# Bottom_Board.net
KiCad netlist of a schematic drawn in EAGLE
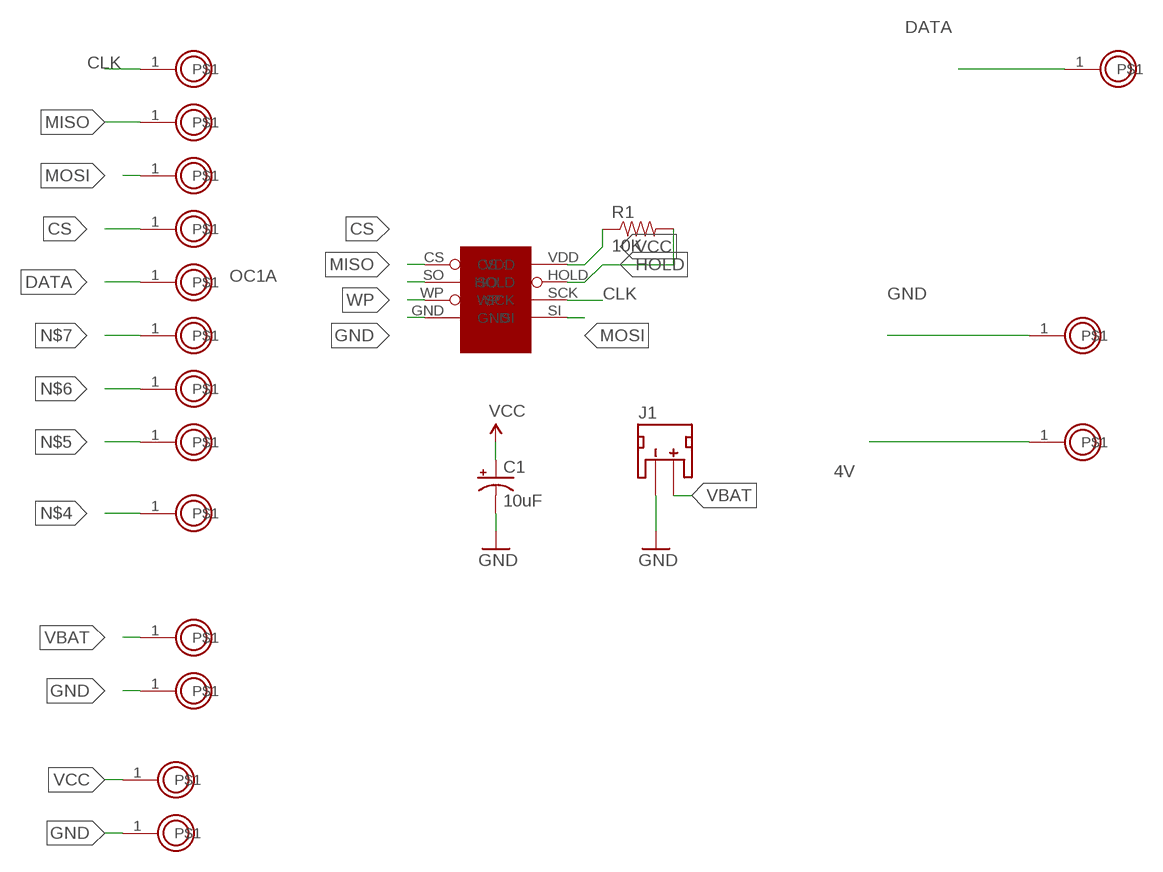
[diagram p0: schematic, sheet 1]

(export (version "E")
  (design (tool "Eeschema 10.0.6"))
  (components
    (comp (ref "0")
      (value "PROTO_POINT")
      (footprint "eagle-import:1X01")
      (libsource (lib "eagle-import") (part "PROTO_POINT"))
    )
    (comp (ref "1")
      (value "PROTO_POINT")
      (footprint "eagle-import:1X01")
      (libsource (lib "eagle-import") (part "PROTO_POINT"))
    )
    (comp (ref "2")
      (value "PROTO_POINT")
      (footprint "eagle-import:1X01")
      (libsource (lib "eagle-import") (part "PROTO_POINT"))
    )
    (comp (ref "3")
      (value "PROTO_POINT")
      (footprint "eagle-import:1X01")
      (libsource (lib "eagle-import") (part "PROTO_POINT"))
    )
    (comp (ref "4")
      (value "PROTO_POINT")
      (footprint "eagle-import:1X01")
      (libsource (lib "eagle-import") (part "PROTO_POINT"))
    )
    (comp (ref "4V")
      (value "PROTO_POINT")
      (footprint "eagle-import:1X01")
      (libsource (lib "eagle-import") (part "PROTO_POINT"))
    )
    (comp (ref "5")
      (value "PROTO_POINT")
      (footprint "eagle-import:1X01")
      (libsource (lib "eagle-import") (part "PROTO_POINT"))
    )
    (comp (ref "A0")
      (value "PROTO_POINT")
      (footprint "eagle-import:1X01")
      (libsource (lib "eagle-import") (part "PROTO_POINT"))
    )
    (comp (ref "A1")
      (value "PROTO_POINT")
      (footprint "eagle-import:1X01")
      (libsource (lib "eagle-import") (part "PROTO_POINT"))
    )
    (comp (ref "BAT")
      (value "PROTO_POINT")
      (footprint "eagle-import:1X01")
      (libsource (lib "eagle-import") (part "PROTO_POINT"))
    )
    (comp (ref "C1")
      (value "10uF")
      (footprint "eagle-import:EIA3216")
      (libsource (lib "eagle-import") (part "10UF-16V-10%(TANT)"))
    )
    (comp (ref "DATA")
      (value "PROTO_POINT")
      (footprint "eagle-import:1X01")
      (libsource (lib "eagle-import") (part "PROTO_POINT"))
    )
    (comp (ref "FRAM")
      (value "MB85RS64V")
      (footprint "eagle-import:SO08")
      (libsource (lib "eagle-import") (part "MB85RS64V"))
    )
    (comp (ref "GND@1")
      (value "PROTO_POINT")
      (footprint "eagle-import:1X01")
      (libsource (lib "eagle-import") (part "PROTO_POINT"))
    )
    (comp (ref "GND@2")
      (value "PROTO_POINT")
      (footprint "eagle-import:1X01")
      (libsource (lib "eagle-import") (part "PROTO_POINT"))
    )
    (comp (ref "GND@3")
      (value "PROTO_POINT")
      (footprint "eagle-import:1X01")
      (libsource (lib "eagle-import") (part "PROTO_POINT"))
    )
    (comp (ref "J1")
      (value "JST_2MM_MALE")
      (footprint "eagle-import:JST-2-SMD")
      (libsource (lib "eagle-import") (part "JST_2MM_MALE"))
    )
    (comp (ref "R1")
      (value "10K")
      (footprint "eagle-import:0603-RES")
      (libsource (lib "eagle-import") (part "10KOHM-1/10W-1%(0603)0603"))
    )
    (comp (ref "RESET")
      (value "PROTO_POINT")
      (footprint "eagle-import:1X01")
      (libsource (lib "eagle-import") (part "PROTO_POINT"))
    )
    (comp (ref "VCC")
      (value "PROTO_POINT")
      (footprint "eagle-import:1X01")
      (libsource (lib "eagle-import") (part "PROTO_POINT"))
    )
  )
  (nets
    (net (code "1") (name "/4V") (class "Default")
      (node (ref "4V") (pin "1") (pinfunction "P$1_1") (pintype "bidirectional"))
    )
    (net (code "2") (name "/CLK") (class "Default")
      (node (ref "5") (pin "1") (pinfunction "P$1_1") (pintype "bidirectional"))
      (node (ref "FRAM") (pin "SCK") (pinfunction "SCK_SCK") (pintype "output"))
    )
    (net (code "3") (name "CS") (class "Default")
      (node (ref "2") (pin "1") (pinfunction "P$1_1") (pintype "bidirectional"))
      (node (ref "FRAM") (pin "CS") (pinfunction "CS_CS") (pintype "input"))
    )
    (net (code "4") (name "DATA") (class "Default")
      (node (ref "1") (pin "1") (pinfunction "P$1_1") (pintype "bidirectional"))
      (node (ref "DATA") (pin "1") (pinfunction "P$1_1") (pintype "bidirectional"))
    )
    (net (code "5") (name "GND") (class "Default")
      (node (ref "C1") (pin "C") (pinfunction "-_C") (pintype "passive"))
      (node (ref "FRAM") (pin "GND") (pinfunction "GND_GND") (pintype "power_in"))
      (node (ref "GND@1") (pin "1") (pinfunction "P$1_1") (pintype "bidirectional"))
      (node (ref "GND@2") (pin "1") (pinfunction "P$1_1") (pintype "bidirectional"))
      (node (ref "GND@3") (pin "1") (pinfunction "P$1_1") (pintype "bidirectional"))
      (node (ref "J1") (pin "1") (pinfunction "-_1") (pintype "bidirectional"))
    )
    (net (code "6") (name "HOLD") (class "Default")
      (node (ref "FRAM") (pin "HOLD") (pinfunction "HOLD_HOLD") (pintype "input"))
      (node (ref "R1") (pin "2") (pinfunction "2_2") (pintype "passive"))
    )
    (net (code "7") (name "MISO") (class "Default")
      (node (ref "4") (pin "1") (pinfunction "P$1_1") (pintype "bidirectional"))
      (node (ref "FRAM") (pin "SO") (pinfunction "SO_SO") (pintype "output"))
    )
    (net (code "8") (name "MOSI") (class "Default")
      (node (ref "3") (pin "1") (pinfunction "P$1_1") (pintype "bidirectional"))
      (node (ref "FRAM") (pin "SI") (pinfunction "SI_SI") (pintype "input"))
    )
    (net (code "9") (name "N$4") (class "Default")
      (node (ref "RESET") (pin "1") (pinfunction "P$1_1") (pintype "bidirectional"))
    )
    (net (code "10") (name "N$5") (class "Default")
      (node (ref "A0") (pin "1") (pinfunction "P$1_1") (pintype "bidirectional"))
    )
    (net (code "11") (name "N$6") (class "Default")
      (node (ref "A1") (pin "1") (pinfunction "P$1_1") (pintype "bidirectional"))
    )
    (net (code "12") (name "N$7") (class "Default")
      (node (ref "0") (pin "1") (pinfunction "P$1_1") (pintype "bidirectional"))
    )
    (net (code "13") (name "VBAT") (class "Default")
      (node (ref "BAT") (pin "1") (pinfunction "P$1_1") (pintype "bidirectional"))
      (node (ref "J1") (pin "2") (pinfunction "+_2") (pintype "bidirectional"))
    )
    (net (code "14") (name "VCC") (class "Default")
      (node (ref "C1") (pin "A") (pinfunction "+_A") (pintype "passive"))
      (node (ref "FRAM") (pin "VDD") (pinfunction "VDD_VDD") (pintype "power_in"))
      (node (ref "R1") (pin "1") (pinfunction "1_1") (pintype "passive"))
      (node (ref "VCC") (pin "1") (pinfunction "P$1_1") (pintype "bidirectional"))
    )
    (net (code "15") (name "WP") (class "Default")
      (node (ref "FRAM") (pin "WP") (pinfunction "WP_WP") (pintype "input"))
    )
    (net (code "16") (name "unconnected-(J1-PAD1-PadNC1)") (class "Default")
      (node (ref "J1") (pin "NC1") (pinfunction "PAD1_NC1") (pintype "bidirectional"))
    )
    (net (code "17") (name "unconnected-(J1-PAD2-PadNC2)") (class "Default")
      (node (ref "J1") (pin "NC2") (pinfunction "PAD2_NC2") (pintype "bidirectional"))
    )
  )
)
